# S04.net
KiCad netlist of a schematic drawn in Altium Designer
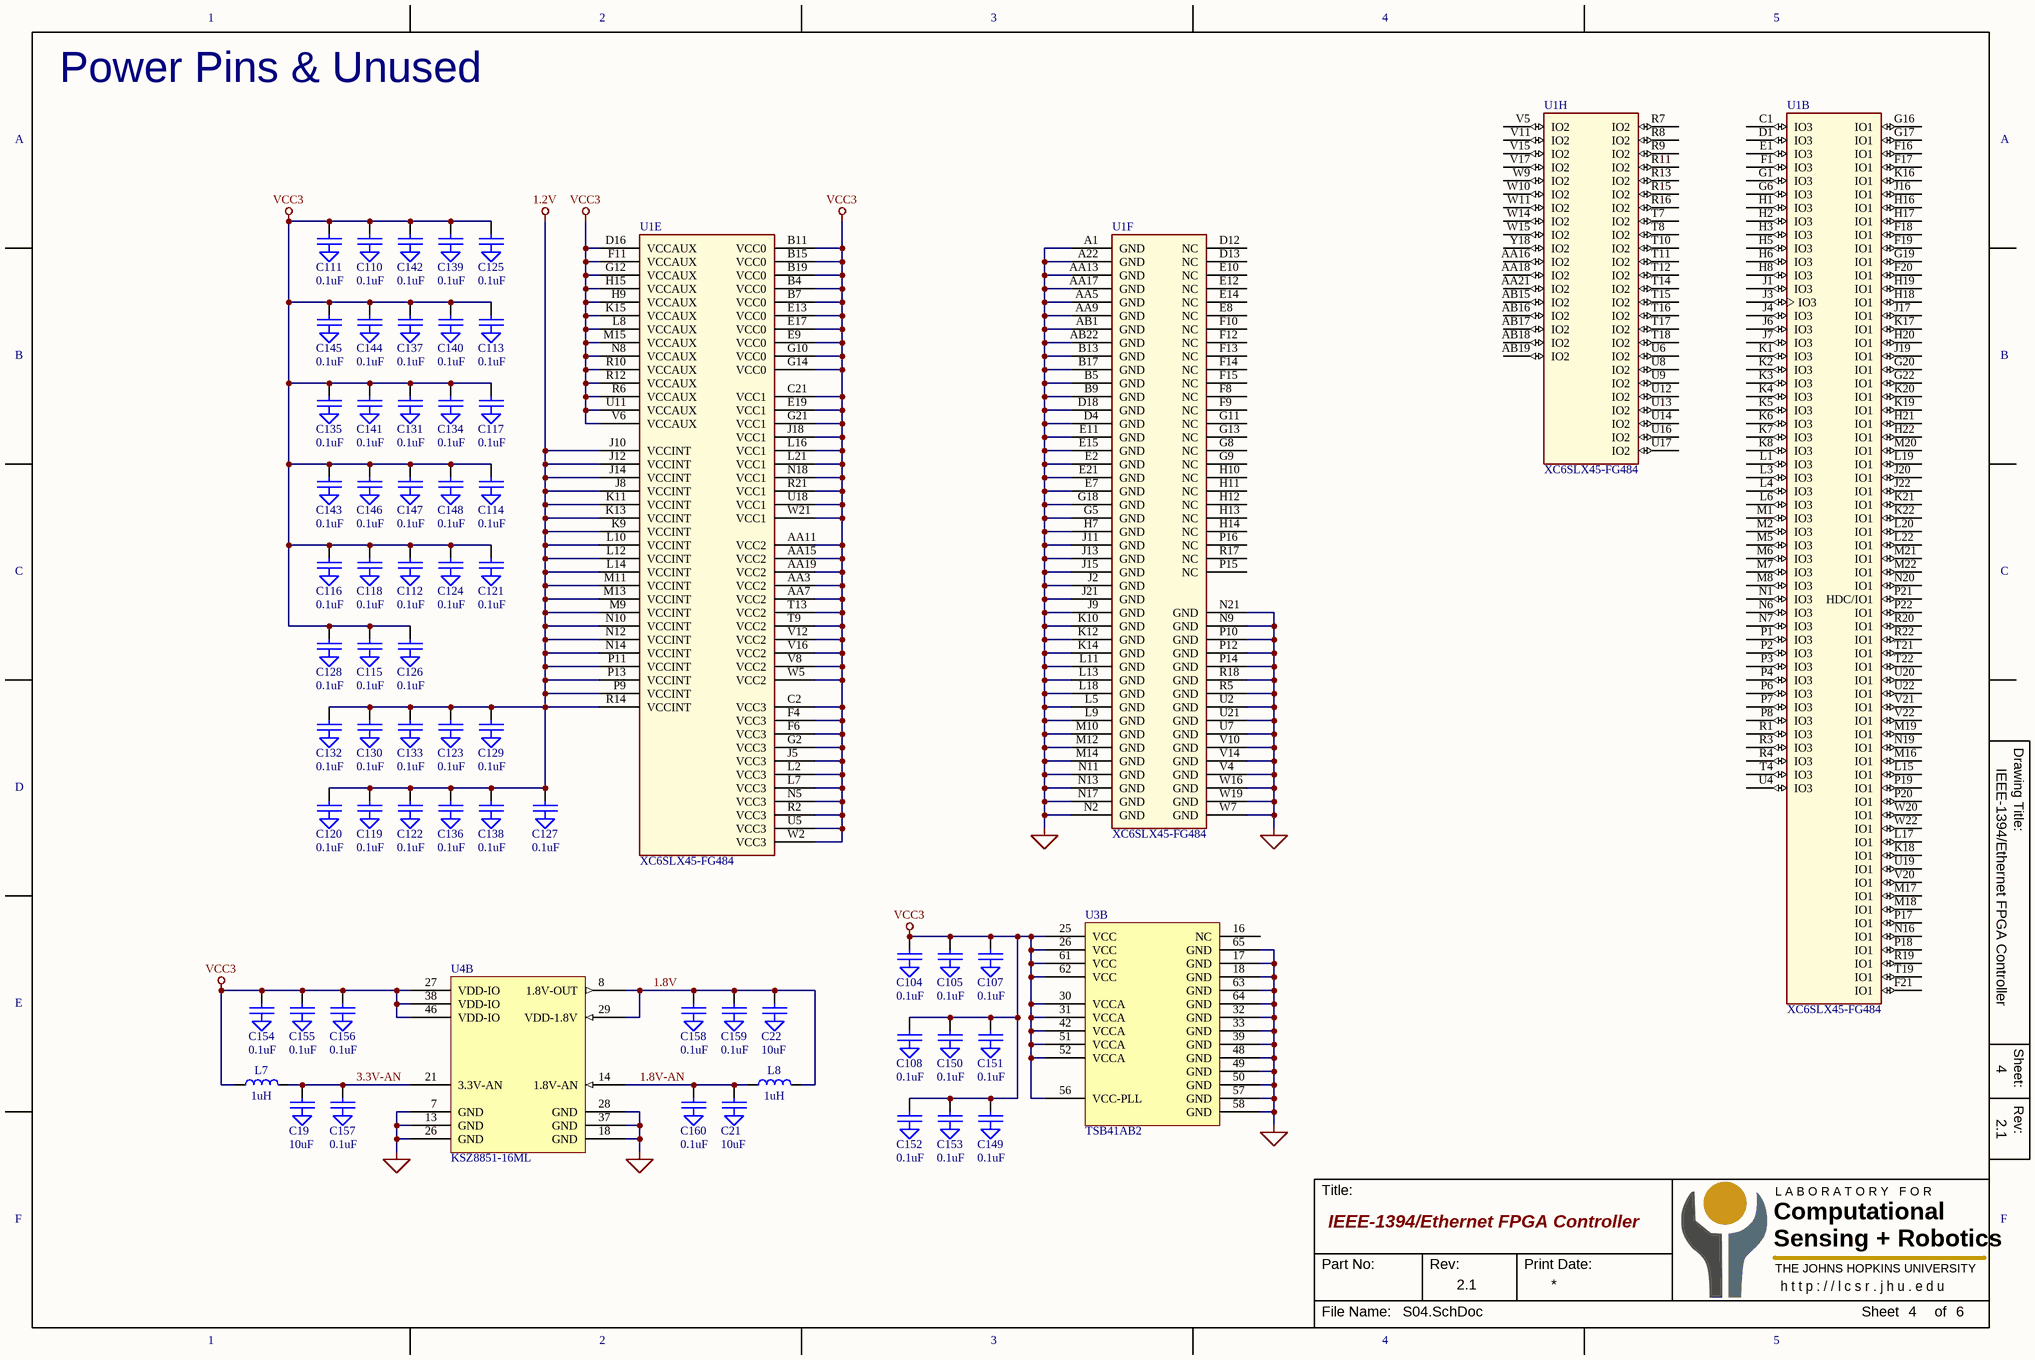
[diagram p0: S04.SchDoc]

(export (version "E")
  (design (tool "Eeschema 10.0.6"))
  (components
    (comp (ref "C19") (value "10uF") (footprint "C0603") (libsource (lib "LibJHU") (part "CAP-GND")))
    (comp (ref "C21") (value "10uF") (footprint "C0603") (libsource (lib "LibJHU") (part "CAP-GND")))
    (comp (ref "C22") (value "10uF") (footprint "C0603") (libsource (lib "LibJHU") (part "CAP-GND")))
    (comp (ref "C104") (value "0.1uF") (footprint "C0402") (libsource (lib "LibJHU") (part "CAP-GND")))
    (comp (ref "C105") (value "0.1uF") (footprint "C0402") (libsource (lib "LibJHU") (part "CAP-GND")))
    (comp (ref "C107") (value "0.1uF") (footprint "C0402") (libsource (lib "LibJHU") (part "CAP-GND")))
    (comp (ref "C108") (value "0.1uF") (footprint "C0402") (libsource (lib "LibJHU") (part "CAP-GND")))
    (comp (ref "C110") (value "0.1uF") (footprint "C0402") (libsource (lib "LibJHU") (part "CAP-GND")))
    (comp (ref "C111") (value "0.1uF") (footprint "C0402") (libsource (lib "LibJHU") (part "CAP-GND")))
    (comp (ref "C112") (value "0.1uF") (footprint "C0402") (libsource (lib "LibJHU") (part "CAP-GND")))
    (comp (ref "C113") (value "0.1uF") (footprint "C0402") (libsource (lib "LibJHU") (part "CAP-GND")))
    (comp (ref "C114") (value "0.1uF") (footprint "C0402") (libsource (lib "LibJHU") (part "CAP-GND")))
    (comp (ref "C115") (value "0.1uF") (footprint "C0402") (libsource (lib "LibJHU") (part "CAP-GND")))
    (comp (ref "C116") (value "0.1uF") (footprint "C0402") (libsource (lib "LibJHU") (part "CAP-GND")))
    (comp (ref "C117") (value "0.1uF") (footprint "C0402") (libsource (lib "LibJHU") (part "CAP-GND")))
    (comp (ref "C118") (value "0.1uF") (footprint "C0402") (libsource (lib "LibJHU") (part "CAP-GND")))
    (comp (ref "C119") (value "0.1uF") (footprint "C0402") (libsource (lib "LibJHU") (part "CAP-GND")))
    (comp (ref "C120") (value "0.1uF") (footprint "C0402") (libsource (lib "LibJHU") (part "CAP-GND")))
    (comp (ref "C121") (value "0.1uF") (footprint "C0402") (libsource (lib "LibJHU") (part "CAP-GND")))
    (comp (ref "C122") (value "0.1uF") (footprint "C0402") (libsource (lib "LibJHU") (part "CAP-GND")))
    (comp (ref "C123") (value "0.1uF") (footprint "C0402") (libsource (lib "LibJHU") (part "CAP-GND")))
    (comp (ref "C124") (value "0.1uF") (footprint "C0402") (libsource (lib "LibJHU") (part "CAP-GND")))
    (comp (ref "C125") (value "0.1uF") (footprint "C0402") (libsource (lib "LibJHU") (part "CAP-GND")))
    (comp (ref "C126") (value "0.1uF") (footprint "C0402") (libsource (lib "LibJHU") (part "CAP-GND")))
    (comp (ref "C127") (value "0.1uF") (footprint "C0402") (libsource (lib "LibJHU") (part "CAP-GND")))
    (comp (ref "C128") (value "0.1uF") (footprint "C0402") (libsource (lib "LibJHU") (part "CAP-GND")))
    (comp (ref "C129") (value "0.1uF") (footprint "C0402") (libsource (lib "LibJHU") (part "CAP-GND")))
    (comp (ref "C130") (value "0.1uF") (footprint "C0402") (libsource (lib "LibJHU") (part "CAP-GND")))
    (comp (ref "C131") (value "0.1uF") (footprint "C0402") (libsource (lib "LibJHU") (part "CAP-GND")))
    (comp (ref "C132") (value "0.1uF") (footprint "C0402") (libsource (lib "LibJHU") (part "CAP-GND")))
    (comp (ref "C133") (value "0.1uF") (footprint "C0402") (libsource (lib "LibJHU") (part "CAP-GND")))
    (comp (ref "C134") (value "0.1uF") (footprint "C0402") (libsource (lib "LibJHU") (part "CAP-GND")))
    (comp (ref "C135") (value "0.1uF") (footprint "C0402") (libsource (lib "LibJHU") (part "CAP-GND")))
    (comp (ref "C136") (value "0.1uF") (footprint "C0402") (libsource (lib "LibJHU") (part "CAP-GND")))
    (comp (ref "C137") (value "0.1uF") (footprint "C0402") (libsource (lib "LibJHU") (part "CAP-GND")))
    (comp (ref "C138") (value "0.1uF") (footprint "C0402") (libsource (lib "LibJHU") (part "CAP-GND")))
    (comp (ref "C139") (value "0.1uF") (footprint "C0402") (libsource (lib "LibJHU") (part "CAP-GND")))
    (comp (ref "C140") (value "0.1uF") (footprint "C0402") (libsource (lib "LibJHU") (part "CAP-GND")))
    (comp (ref "C141") (value "0.1uF") (footprint "C0402") (libsource (lib "LibJHU") (part "CAP-GND")))
    (comp (ref "C142") (value "0.1uF") (footprint "C0402") (libsource (lib "LibJHU") (part "CAP-GND")))
    (comp (ref "C143") (value "0.1uF") (footprint "C0402") (libsource (lib "LibJHU") (part "CAP-GND")))
    (comp (ref "C144") (value "0.1uF") (footprint "C0402") (libsource (lib "LibJHU") (part "CAP-GND")))
    (comp (ref "C145") (value "0.1uF") (footprint "C0402") (libsource (lib "LibJHU") (part "CAP-GND")))
    (comp (ref "C146") (value "0.1uF") (footprint "C0402") (libsource (lib "LibJHU") (part "CAP-GND")))
    (comp (ref "C147") (value "0.1uF") (footprint "C0402") (libsource (lib "LibJHU") (part "CAP-GND")))
    (comp (ref "C148") (value "0.1uF") (footprint "C0402") (libsource (lib "LibJHU") (part "CAP-GND")))
    (comp (ref "C149") (value "0.1uF") (footprint "C0402") (libsource (lib "LibJHU") (part "CAP-GND")))
    (comp (ref "C150") (value "0.1uF") (footprint "C0402") (libsource (lib "LibJHU") (part "CAP-GND")))
    (comp (ref "C151") (value "0.1uF") (footprint "C0402") (libsource (lib "LibJHU") (part "CAP-GND")))
    (comp (ref "C152") (value "0.1uF") (footprint "C0402") (libsource (lib "LibJHU") (part "CAP-GND")))
    (comp (ref "C153") (value "0.1uF") (footprint "C0402") (libsource (lib "LibJHU") (part "CAP-GND")))
    (comp (ref "C154") (value "0.1uF") (footprint "C0402") (libsource (lib "LibJHU") (part "CAP-GND")))
    (comp (ref "C155") (value "0.1uF") (footprint "C0402") (libsource (lib "LibJHU") (part "CAP-GND")))
    (comp (ref "C156") (value "0.1uF") (footprint "C0402") (libsource (lib "LibJHU") (part "CAP-GND")))
    (comp (ref "C157") (value "0.1uF") (footprint "C0402") (libsource (lib "LibJHU") (part "CAP-GND")))
    (comp (ref "C158") (value "0.1uF") (footprint "C0402") (libsource (lib "LibJHU") (part "CAP-GND")))
    (comp (ref "C159") (value "0.1uF") (footprint "C0402") (libsource (lib "LibJHU") (part "CAP-GND")))
    (comp (ref "C160") (value "0.1uF") (footprint "C0402") (libsource (lib "LibJHU") (part "CAP-GND")))
    (comp (ref "L7") (value "1uH") (footprint "L0603") (libsource (lib "LibJHU") (part "INDUCTOR")))
    (comp (ref "L8") (value "1uH") (footprint "L0603") (libsource (lib "LibJHU") (part "INDUCTOR")))
    (comp (ref "U1")
      (value "XC6SLX45-FG484")
      (footprint "FG-484")
      (libsource (lib "LibJHU") (part "XC6SLX45-FG484"))
    )
    (comp (ref "U3")
      (value "TSB41AB2")
      (footprint "PQFP-65")
      (description "IEEE 1394a-2000 Two-port Transceiver/Arbiter")
      (libsource (lib "LibJHU") (part "TSB41AB2"))
    )
    (comp (ref "U4")
      (value "KSZ8851-16ML")
      (footprint "QFP-48-7MM")
      (libsource (lib "LibJHU") (part "KSZ8851-16ML"))
    )
  )
  (nets
    (net (code "1") (name "/1.8V") (class "Default")
      (node (ref "C158") (pin "1") (pintype "passive"))
      (node (ref "C159") (pin "1") (pintype "passive"))
      (node (ref "C22") (pin "1") (pintype "passive"))
      (node (ref "L8") (pin "2") (pintype "passive"))
      (node (ref "U4") (pin "29") (pinfunction "VDD-1.8V_29") (pintype "input"))
      (node (ref "U4") (pin "8") (pinfunction "1.8V-OUT_8") (pintype "output"))
    )
    (net (code "2") (name "/1.8V-AN") (class "Default")
      (node (ref "C160") (pin "1") (pintype "passive"))
      (node (ref "C21") (pin "1") (pintype "passive"))
      (node (ref "L8") (pin "1") (pintype "passive"))
      (node (ref "U4") (pin "14") (pinfunction "1.8V-AN_14") (pintype "input"))
    )
    (net (code "3") (name "/3.3V-AN") (class "Default")
      (node (ref "C157") (pin "1") (pintype "passive"))
      (node (ref "C19") (pin "1") (pintype "passive"))
      (node (ref "L7") (pin "2") (pintype "passive"))
      (node (ref "U4") (pin "21") (pinfunction "3.3V-AN_21") (pintype "power_in"))
    )
    (net (code "4") (name "1.2V") (class "Default")
      (node (ref "C119") (pin "1") (pintype "passive"))
      (node (ref "C120") (pin "1") (pintype "passive"))
      (node (ref "C122") (pin "1") (pintype "passive"))
      (node (ref "C123") (pin "1") (pintype "passive"))
      (node (ref "C127") (pin "1") (pintype "passive"))
      (node (ref "C129") (pin "1") (pintype "passive"))
      (node (ref "C130") (pin "1") (pintype "passive"))
      (node (ref "C132") (pin "1") (pintype "passive"))
      (node (ref "C133") (pin "1") (pintype "passive"))
      (node (ref "C136") (pin "1") (pintype "passive"))
      (node (ref "C138") (pin "1") (pintype "passive"))
      (node (ref "U1") (pin "J10") (pinfunction "VCCINT_J10") (pintype "power_in"))
      (node (ref "U1") (pin "J12") (pinfunction "VCCINT_J12") (pintype "power_in"))
      (node (ref "U1") (pin "J14") (pinfunction "VCCINT_J14") (pintype "power_in"))
      (node (ref "U1") (pin "J8") (pinfunction "VCCINT_J8") (pintype "power_in"))
      (node (ref "U1") (pin "K11") (pinfunction "VCCINT_K11") (pintype "power_in"))
      (node (ref "U1") (pin "K13") (pinfunction "VCCINT_K13") (pintype "power_in"))
      (node (ref "U1") (pin "K9") (pinfunction "VCCINT_K9") (pintype "power_in"))
      (node (ref "U1") (pin "L10") (pinfunction "VCCINT_L10") (pintype "power_in"))
      (node (ref "U1") (pin "L12") (pinfunction "VCCINT_L12") (pintype "power_in"))
      (node (ref "U1") (pin "L14") (pinfunction "VCCINT_L14") (pintype "power_in"))
      (node (ref "U1") (pin "M11") (pinfunction "VCCINT_M11") (pintype "power_in"))
      (node (ref "U1") (pin "M13") (pinfunction "VCCINT_M13") (pintype "power_in"))
      (node (ref "U1") (pin "M9") (pinfunction "VCCINT_M9") (pintype "power_in"))
      (node (ref "U1") (pin "N10") (pinfunction "VCCINT_N10") (pintype "power_in"))
      (node (ref "U1") (pin "N12") (pinfunction "VCCINT_N12") (pintype "power_in"))
      (node (ref "U1") (pin "N14") (pinfunction "VCCINT_N14") (pintype "power_in"))
      (node (ref "U1") (pin "P11") (pinfunction "VCCINT_P11") (pintype "power_in"))
      (node (ref "U1") (pin "P13") (pinfunction "VCCINT_P13") (pintype "power_in"))
      (node (ref "U1") (pin "P9") (pinfunction "VCCINT_P9") (pintype "power_in"))
      (node (ref "U1") (pin "R14") (pinfunction "VCCINT_R14") (pintype "power_in"))
    )
    (net (code "5") (name "GND") (class "Default")
      (node (ref "C104") (pin "2") (pinfunction "GND_2") (pintype "power_in"))
      (node (ref "C105") (pin "2") (pinfunction "GND_2") (pintype "power_in"))
      (node (ref "C107") (pin "2") (pinfunction "GND_2") (pintype "power_in"))
      (node (ref "C108") (pin "2") (pinfunction "GND_2") (pintype "power_in"))
      (node (ref "C110") (pin "2") (pinfunction "GND_2") (pintype "power_in"))
      (node (ref "C111") (pin "2") (pinfunction "GND_2") (pintype "power_in"))
      (node (ref "C112") (pin "2") (pinfunction "GND_2") (pintype "power_in"))
      (node (ref "C113") (pin "2") (pinfunction "GND_2") (pintype "power_in"))
      (node (ref "C114") (pin "2") (pinfunction "GND_2") (pintype "power_in"))
      (node (ref "C115") (pin "2") (pinfunction "GND_2") (pintype "power_in"))
      (node (ref "C116") (pin "2") (pinfunction "GND_2") (pintype "power_in"))
      (node (ref "C117") (pin "2") (pinfunction "GND_2") (pintype "power_in"))
      (node (ref "C118") (pin "2") (pinfunction "GND_2") (pintype "power_in"))
      (node (ref "C119") (pin "2") (pinfunction "GND_2") (pintype "power_in"))
      (node (ref "C120") (pin "2") (pinfunction "GND_2") (pintype "power_in"))
      (node (ref "C121") (pin "2") (pinfunction "GND_2") (pintype "power_in"))
      (node (ref "C122") (pin "2") (pinfunction "GND_2") (pintype "power_in"))
      (node (ref "C123") (pin "2") (pinfunction "GND_2") (pintype "power_in"))
      (node (ref "C124") (pin "2") (pinfunction "GND_2") (pintype "power_in"))
      (node (ref "C125") (pin "2") (pinfunction "GND_2") (pintype "power_in"))
      (node (ref "C126") (pin "2") (pinfunction "GND_2") (pintype "power_in"))
      (node (ref "C127") (pin "2") (pinfunction "GND_2") (pintype "power_in"))
      (node (ref "C128") (pin "2") (pinfunction "GND_2") (pintype "power_in"))
      (node (ref "C129") (pin "2") (pinfunction "GND_2") (pintype "power_in"))
      (node (ref "C130") (pin "2") (pinfunction "GND_2") (pintype "power_in"))
      (node (ref "C131") (pin "2") (pinfunction "GND_2") (pintype "power_in"))
      (node (ref "C132") (pin "2") (pinfunction "GND_2") (pintype "power_in"))
      (node (ref "C133") (pin "2") (pinfunction "GND_2") (pintype "power_in"))
      (node (ref "C134") (pin "2") (pinfunction "GND_2") (pintype "power_in"))
      (node (ref "C135") (pin "2") (pinfunction "GND_2") (pintype "power_in"))
      (node (ref "C136") (pin "2") (pinfunction "GND_2") (pintype "power_in"))
      (node (ref "C137") (pin "2") (pinfunction "GND_2") (pintype "power_in"))
      (node (ref "C138") (pin "2") (pinfunction "GND_2") (pintype "power_in"))
      (node (ref "C139") (pin "2") (pinfunction "GND_2") (pintype "power_in"))
      (node (ref "C140") (pin "2") (pinfunction "GND_2") (pintype "power_in"))
      (node (ref "C141") (pin "2") (pinfunction "GND_2") (pintype "power_in"))
      (node (ref "C142") (pin "2") (pinfunction "GND_2") (pintype "power_in"))
      (node (ref "C143") (pin "2") (pinfunction "GND_2") (pintype "power_in"))
      (node (ref "C144") (pin "2") (pinfunction "GND_2") (pintype "power_in"))
      (node (ref "C145") (pin "2") (pinfunction "GND_2") (pintype "power_in"))
      (node (ref "C146") (pin "2") (pinfunction "GND_2") (pintype "power_in"))
      (node (ref "C147") (pin "2") (pinfunction "GND_2") (pintype "power_in"))
      (node (ref "C148") (pin "2") (pinfunction "GND_2") (pintype "power_in"))
      (node (ref "C149") (pin "2") (pinfunction "GND_2") (pintype "power_in"))
      (node (ref "C150") (pin "2") (pinfunction "GND_2") (pintype "power_in"))
      (node (ref "C151") (pin "2") (pinfunction "GND_2") (pintype "power_in"))
      (node (ref "C152") (pin "2") (pinfunction "GND_2") (pintype "power_in"))
      (node (ref "C153") (pin "2") (pinfunction "GND_2") (pintype "power_in"))
      (node (ref "C154") (pin "2") (pinfunction "GND_2") (pintype "power_in"))
      (node (ref "C155") (pin "2") (pinfunction "GND_2") (pintype "power_in"))
      (node (ref "C156") (pin "2") (pinfunction "GND_2") (pintype "power_in"))
      (node (ref "C157") (pin "2") (pinfunction "GND_2") (pintype "power_in"))
      (node (ref "C158") (pin "2") (pinfunction "GND_2") (pintype "power_in"))
      (node (ref "C159") (pin "2") (pinfunction "GND_2") (pintype "power_in"))
      (node (ref "C160") (pin "2") (pinfunction "GND_2") (pintype "power_in"))
      (node (ref "C19") (pin "2") (pinfunction "GND_2") (pintype "power_in"))
      (node (ref "C21") (pin "2") (pinfunction "GND_2") (pintype "power_in"))
      (node (ref "C22") (pin "2") (pinfunction "GND_2") (pintype "power_in"))
      (node (ref "U1") (pin "A1") (pinfunction "GND_A1") (pintype "power_in"))
      (node (ref "U1") (pin "A22") (pinfunction "GND_A22") (pintype "power_in"))
      (node (ref "U1") (pin "AA13") (pinfunction "GND_AA13") (pintype "power_in"))
      (node (ref "U1") (pin "AA17") (pinfunction "GND_AA17") (pintype "power_in"))
      (node (ref "U1") (pin "AA5") (pinfunction "GND_AA5") (pintype "power_in"))
      (node (ref "U1") (pin "AA9") (pinfunction "GND_AA9") (pintype "power_in"))
      (node (ref "U1") (pin "AB1") (pinfunction "GND_AB1") (pintype "power_in"))
      (node (ref "U1") (pin "AB22") (pinfunction "GND_AB22") (pintype "power_in"))
      (node (ref "U1") (pin "B13") (pinfunction "GND_B13") (pintype "power_in"))
      (node (ref "U1") (pin "B17") (pinfunction "GND_B17") (pintype "power_in"))
      (node (ref "U1") (pin "B5") (pinfunction "GND_B5") (pintype "power_in"))
      (node (ref "U1") (pin "B9") (pinfunction "GND_B9") (pintype "power_in"))
      (node (ref "U1") (pin "D18") (pinfunction "GND_D18") (pintype "power_in"))
      (node (ref "U1") (pin "D4") (pinfunction "GND_D4") (pintype "power_in"))
      (node (ref "U1") (pin "E11") (pinfunction "GND_E11") (pintype "power_in"))
      (node (ref "U1") (pin "E15") (pinfunction "GND_E15") (pintype "power_in"))
      (node (ref "U1") (pin "E2") (pinfunction "GND_E2") (pintype "power_in"))
      (node (ref "U1") (pin "E21") (pinfunction "GND_E21") (pintype "power_in"))
      (node (ref "U1") (pin "E7") (pinfunction "GND_E7") (pintype "power_in"))
      (node (ref "U1") (pin "G18") (pinfunction "GND_G18") (pintype "power_in"))
      (node (ref "U1") (pin "G5") (pinfunction "GND_G5") (pintype "power_in"))
      (node (ref "U1") (pin "H7") (pinfunction "GND_H7") (pintype "power_in"))
      (node (ref "U1") (pin "J11") (pinfunction "GND_J11") (pintype "power_in"))
      (node (ref "U1") (pin "J13") (pinfunction "GND_J13") (pintype "power_in"))
      (node (ref "U1") (pin "J15") (pinfunction "GND_J15") (pintype "power_in"))
      (node (ref "U1") (pin "J2") (pinfunction "GND_J2") (pintype "power_in"))
      (node (ref "U1") (pin "J21") (pinfunction "GND_J21") (pintype "power_in"))
      (node (ref "U1") (pin "J9") (pinfunction "GND_J9") (pintype "power_in"))
      (node (ref "U1") (pin "K10") (pinfunction "GND_K10") (pintype "power_in"))
      (node (ref "U1") (pin "K12") (pinfunction "GND_K12") (pintype "power_in"))
      (node (ref "U1") (pin "K14") (pinfunction "GND_K14") (pintype "power_in"))
      (node (ref "U1") (pin "L11") (pinfunction "GND_L11") (pintype "power_in"))
      (node (ref "U1") (pin "L13") (pinfunction "GND_L13") (pintype "power_in"))
      (node (ref "U1") (pin "L18") (pinfunction "GND_L18") (pintype "power_in"))
      (node (ref "U1") (pin "L5") (pinfunction "GND_L5") (pintype "power_in"))
      (node (ref "U1") (pin "L9") (pinfunction "GND_L9") (pintype "power_in"))
      (node (ref "U1") (pin "M10") (pinfunction "GND_M10") (pintype "power_in"))
      (node (ref "U1") (pin "M12") (pinfunction "GND_M12") (pintype "power_in"))
      (node (ref "U1") (pin "M14") (pinfunction "GND_M14") (pintype "power_in"))
      (node (ref "U1") (pin "N11") (pinfunction "GND_N11") (pintype "power_in"))
      (node (ref "U1") (pin "N13") (pinfunction "GND_N13") (pintype "power_in"))
      (node (ref "U1") (pin "N17") (pinfunction "GND_N17") (pintype "power_in"))
      (node (ref "U1") (pin "N2") (pinfunction "GND_N2") (pintype "power_in"))
      (node (ref "U1") (pin "N21") (pinfunction "GND_N21") (pintype "power_in"))
      (node (ref "U1") (pin "N9") (pinfunction "GND_N9") (pintype "power_in"))
      (node (ref "U1") (pin "P10") (pinfunction "GND_P10") (pintype "power_in"))
      (node (ref "U1") (pin "P12") (pinfunction "GND_P12") (pintype "power_in"))
      (node (ref "U1") (pin "P14") (pinfunction "GND_P14") (pintype "power_in"))
      (node (ref "U1") (pin "R18") (pinfunction "GND_R18") (pintype "power_in"))
      (node (ref "U1") (pin "R5") (pinfunction "GND_R5") (pintype "power_in"))
      (node (ref "U1") (pin "U2") (pinfunction "GND_U2") (pintype "power_in"))
      (node (ref "U1") (pin "U21") (pinfunction "GND_U21") (pintype "power_in"))
      (node (ref "U1") (pin "U7") (pinfunction "GND_U7") (pintype "power_in"))
      (node (ref "U1") (pin "V10") (pinfunction "GND_V10") (pintype "power_in"))
      (node (ref "U1") (pin "V14") (pinfunction "GND_V14") (pintype "power_in"))
      (node (ref "U1") (pin "V4") (pinfunction "GND_V4") (pintype "power_in"))
      (node (ref "U1") (pin "W16") (pinfunction "GND_W16") (pintype "power_in"))
      (node (ref "U1") (pin "W19") (pinfunction "GND_W19") (pintype "power_in"))
      (node (ref "U1") (pin "W7") (pinfunction "GND_W7") (pintype "power_in"))
      (node (ref "U3") (pin "17") (pinfunction "GND_17") (pintype "power_in"))
      (node (ref "U3") (pin "18") (pinfunction "GND_18") (pintype "power_in"))
      (node (ref "U3") (pin "32") (pinfunction "GND_32") (pintype "power_in"))
      (node (ref "U3") (pin "33") (pinfunction "GND_33") (pintype "power_in"))
      (node (ref "U3") (pin "39") (pinfunction "GND_39") (pintype "power_in"))
      (node (ref "U3") (pin "48") (pinfunction "GND_48") (pintype "power_in"))
      (node (ref "U3") (pin "49") (pinfunction "GND_49") (pintype "power_in"))
      (node (ref "U3") (pin "50") (pinfunction "GND_50") (pintype "power_in"))
      (node (ref "U3") (pin "57") (pinfunction "GND_57") (pintype "power_in"))
      (node (ref "U3") (pin "58") (pinfunction "GND_58") (pintype "power_in"))
      (node (ref "U3") (pin "63") (pinfunction "GND_63") (pintype "power_in"))
      (node (ref "U3") (pin "64") (pinfunction "GND_64") (pintype "power_in"))
      (node (ref "U3") (pin "65") (pinfunction "GND_65") (pintype "power_in"))
      (node (ref "U4") (pin "13") (pinfunction "GND_13") (pintype "power_in"))
      (node (ref "U4") (pin "18") (pinfunction "GND_18") (pintype "power_in"))
      (node (ref "U4") (pin "26") (pinfunction "GND_26") (pintype "power_in"))
      (node (ref "U4") (pin "28") (pinfunction "GND_28") (pintype "power_in"))
      (node (ref "U4") (pin "37") (pinfunction "GND_37") (pintype "power_in"))
      (node (ref "U4") (pin "7") (pinfunction "GND_7") (pintype "power_in"))
    )
    (net (code "6") (name "VCC3") (class "Default")
      (node (ref "C104") (pin "1") (pintype "passive"))
      (node (ref "C105") (pin "1") (pintype "passive"))
      (node (ref "C107") (pin "1") (pintype "passive"))
      (node (ref "C108") (pin "1") (pintype "passive"))
      (node (ref "C110") (pin "1") (pintype "passive"))
      (node (ref "C111") (pin "1") (pintype "passive"))
      (node (ref "C112") (pin "1") (pintype "passive"))
      (node (ref "C113") (pin "1") (pintype "passive"))
      (node (ref "C114") (pin "1") (pintype "passive"))
      (node (ref "C115") (pin "1") (pintype "passive"))
      (node (ref "C116") (pin "1") (pintype "passive"))
      (node (ref "C117") (pin "1") (pintype "passive"))
      (node (ref "C118") (pin "1") (pintype "passive"))
      (node (ref "C121") (pin "1") (pintype "passive"))
      (node (ref "C124") (pin "1") (pintype "passive"))
      (node (ref "C125") (pin "1") (pintype "passive"))
      (node (ref "C126") (pin "1") (pintype "passive"))
      (node (ref "C128") (pin "1") (pintype "passive"))
      (node (ref "C131") (pin "1") (pintype "passive"))
      (node (ref "C134") (pin "1") (pintype "passive"))
      (node (ref "C135") (pin "1") (pintype "passive"))
      (node (ref "C137") (pin "1") (pintype "passive"))
      (node (ref "C139") (pin "1") (pintype "passive"))
      (node (ref "C140") (pin "1") (pintype "passive"))
      (node (ref "C141") (pin "1") (pintype "passive"))
      (node (ref "C142") (pin "1") (pintype "passive"))
      (node (ref "C143") (pin "1") (pintype "passive"))
      (node (ref "C144") (pin "1") (pintype "passive"))
      (node (ref "C145") (pin "1") (pintype "passive"))
      (node (ref "C146") (pin "1") (pintype "passive"))
      (node (ref "C147") (pin "1") (pintype "passive"))
      (node (ref "C148") (pin "1") (pintype "passive"))
      (node (ref "C149") (pin "1") (pintype "passive"))
      (node (ref "C150") (pin "1") (pintype "passive"))
      (node (ref "C151") (pin "1") (pintype "passive"))
      (node (ref "C152") (pin "1") (pintype "passive"))
      (node (ref "C153") (pin "1") (pintype "passive"))
      (node (ref "C154") (pin "1") (pintype "passive"))
      (node (ref "C155") (pin "1") (pintype "passive"))
      (node (ref "C156") (pin "1") (pintype "passive"))
      (node (ref "L7") (pin "1") (pintype "passive"))
      (node (ref "U1") (pin "AA11") (pinfunction "VCC2_AA11") (pintype "power_in"))
      (node (ref "U1") (pin "AA15") (pinfunction "VCC2_AA15") (pintype "power_in"))
      (node (ref "U1") (pin "AA19") (pinfunction "VCC2_AA19") (pintype "power_in"))
      (node (ref "U1") (pin "AA3") (pinfunction "VCC2_AA3") (pintype "power_in"))
      (node (ref "U1") (pin "AA7") (pinfunction "VCC2_AA7") (pintype "power_in"))
      (node (ref "U1") (pin "B11") (pinfunction "VCC0_B11") (pintype "power_in"))
      (node (ref "U1") (pin "B15") (pinfunction "VCC0_B15") (pintype "power_in"))
      (node (ref "U1") (pin "B19") (pinfunction "VCC0_B19") (pintype "power_in"))
      (node (ref "U1") (pin "B4") (pinfunction "VCC0_B4") (pintype "power_in"))
      (node (ref "U1") (pin "B7") (pinfunction "VCC0_B7") (pintype "power_in"))
      (node (ref "U1") (pin "C2") (pinfunction "VCC3_C2") (pintype "power_in"))
      (node (ref "U1") (pin "C21") (pinfunction "VCC1_C21") (pintype "power_in"))
      (node (ref "U1") (pin "D16") (pinfunction "VCCAUX_D16") (pintype "power_in"))
      (node (ref "U1") (pin "E13") (pinfunction "VCC0_E13") (pintype "power_in"))
      (node (ref "U1") (pin "E17") (pinfunction "VCC0_E17") (pintype "power_in"))
      (node (ref "U1") (pin "E19") (pinfunction "VCC1_E19") (pintype "power_in"))
      (node (ref "U1") (pin "E9") (pinfunction "VCC0_E9") (pintype "power_in"))
      (node (ref "U1") (pin "F11") (pinfunction "VCCAUX_F11") (pintype "power_in"))
      (node (ref "U1") (pin "F4") (pinfunction "VCC3_F4") (pintype "power_in"))
      (node (ref "U1") (pin "F6") (pinfunction "VCC3_F6") (pintype "power_in"))
      (node (ref "U1") (pin "G10") (pinfunction "VCC0_G10") (pintype "power_in"))
      (node (ref "U1") (pin "G12") (pinfunction "VCCAUX_G12") (pintype "power_in"))
      (node (ref "U1") (pin "G14") (pinfunction "VCC0_G14") (pintype "power_in"))
      (node (ref "U1") (pin "G2") (pinfunction "VCC3_G2") (pintype "power_in"))
      (node (ref "U1") (pin "G21") (pinfunction "VCC1_G21") (pintype "power_in"))
      (node (ref "U1") (pin "H15") (pinfunction "VCCAUX_H15") (pintype "power_in"))
      (node (ref "U1") (pin "H9") (pinfunction "VCCAUX_H9") (pintype "power_in"))
      (node (ref "U1") (pin "J18") (pinfunction "VCC1_J18") (pintype "power_in"))
      (node (ref "U1") (pin "J5") (pinfunction "VCC3_J5") (pintype "power_in"))
      (node (ref "U1") (pin "K15") (pinfunction "VCCAUX_K15") (pintype "power_in"))
      (node (ref "U1") (pin "L16") (pinfunction "VCC1_L16") (pintype "power_in"))
      (node (ref "U1") (pin "L2") (pinfunction "VCC3_L2") (pintype "power_in"))
      (node (ref "U1") (pin "L21") (pinfunction "VCC1_L21") (pintype "power_in"))
      (node (ref "U1") (pin "L7") (pinfunction "VCC3_L7") (pintype "power_in"))
      (node (ref "U1") (pin "L8") (pinfunction "VCCAUX_L8") (pintype "power_in"))
      (node (ref "U1") (pin "M15") (pinfunction "VCCAUX_M15") (pintype "power_in"))
      (node (ref "U1") (pin "N18") (pinfunction "VCC1_N18") (pintype "power_in"))
      (node (ref "U1") (pin "N5") (pinfunction "VCC3_N5") (pintype "power_in"))
      (node (ref "U1") (pin "N8") (pinfunction "VCCAUX_N8") (pintype "power_in"))
      (node (ref "U1") (pin "R10") (pinfunction "VCCAUX_R10") (pintype "power_in"))
      (node (ref "U1") (pin "R12") (pinfunction "VCCAUX_R12") (pintype "power_in"))
      (node (ref "U1") (pin "R2") (pinfunction "VCC3_R2") (pintype "power_in"))
      (node (ref "U1") (pin "R21") (pinfunction "VCC1_R21") (pintype "power_in"))
      (node (ref "U1") (pin "R6") (pinfunction "VCCAUX_R6") (pintype "power_in"))
      (node (ref "U1") (pin "T13") (pinfunction "VCC2_T13") (pintype "power_in"))
      (node (ref "U1") (pin "T9") (pinfunction "VCC2_T9") (pintype "power_in"))
      (node (ref "U1") (pin "U11") (pinfunction "VCCAUX_U11") (pintype "power_in"))
      (node (ref "U1") (pin "U18") (pinfunction "VCC1_U18") (pintype "power_in"))
      (node (ref "U1") (pin "U5") (pinfunction "VCC3_U5") (pintype "power_in"))
      (node (ref "U1") (pin "V12") (pinfunction "VCC2_V12") (pintype "power_in"))
      (node (ref "U1") (pin "V16") (pinfunction "VCC2_V16") (pintype "power_in"))
      (node (ref "U1") (pin "V6") (pinfunction "VCCAUX_V6") (pintype "power_in"))
      (node (ref "U1") (pin "V8") (pinfunction "VCC2_V8") (pintype "power_in"))
      (node (ref "U1") (pin "W2") (pinfunction "VCC3_W2") (pintype "power_in"))
      (node (ref "U1") (pin "W21") (pinfunction "VCC1_W21") (pintype "power_in"))
      (node (ref "U1") (pin "W5") (pinfunction "VCC2_W5") (pintype "power_in"))
      (node (ref "U3") (pin "25") (pinfunction "VCC_25") (pintype "power_in"))
      (node (ref "U3") (pin "26") (pinfunction "VCC_26") (pintype "power_in"))
      (node (ref "U3") (pin "30") (pinfunction "VCCA_30") (pintype "power_in"))
      (node (ref "U3") (pin "31") (pinfunction "VCCA_31") (pintype "power_in"))
      (node (ref "U3") (pin "42") (pinfunction "VCCA_42") (pintype "power_in"))
      (node (ref "U3") (pin "51") (pinfunction "VCCA_51") (pintype "power_in"))
      (node (ref "U3") (pin "52") (pinfunction "VCCA_52") (pintype "power_in"))
      (node (ref "U3") (pin "56") (pinfunction "VCC-PLL_56") (pintype "power_in"))
      (node (ref "U3") (pin "61") (pinfunction "VCC_61") (pintype "power_in"))
      (node (ref "U3") (pin "62") (pinfunction "VCC_62") (pintype "power_in"))
      (node (ref "U4") (pin "27") (pinfunction "VDD-IO_27") (pintype "power_in"))
      (node (ref "U4") (pin "38") (pinfunction "VDD-IO_38") (pintype "power_in"))
      (node (ref "U4") (pin "46") (pinfunction "VDD-IO_46") (pintype "power_in"))
    )
    (net (code "7") (name "unconnected-(U1B-HDC{slash}IO1-PadP21)") (class "Default")
      (node (ref "U1") (pin "P21") (pinfunction "HDC/IO1_P21") (pintype "bidirectional"))
    )
    (net (code "8") (name "unconnected-(U1B-IO1-PadF16)") (class "Default")
      (node (ref "U1") (pin "F16") (pinfunction "IO1_F16") (pintype "bidirectional"))
    )
    (net (code "9") (name "unconnected-(U1B-IO1-PadF17)") (class "Default")
      (node (ref "U1") (pin "F17") (pinfunction "IO1_F17") (pintype "bidirectional"))
    )
    (net (code "10") (name "unconnected-(U1B-IO1-PadF18)") (class "Default")
      (node (ref "U1") (pin "F18") (pinfunction "IO1_F18") (pintype "bidirectional"))
    )
    (net (code "11") (name "unconnected-(U1B-IO1-PadF19)") (class "Default")
      (node (ref "U1") (pin "F19") (pinfunction "IO1_F19") (pintype "bidirectional"))
    )
    (net (code "12") (name "unconnected-(U1B-IO1-PadF20)") (class "Default")
      (node (ref "U1") (pin "F20") (pinfunction "IO1_F20") (pintype "bidirectional"))
    )
    (net (code "13") (name "unconnected-(U1B-IO1-PadF21)") (class "Default")
      (node (ref "U1") (pin "F21") (pinfunction "IO1_F21") (pintype "bidirectional"))
    )
    (net (code "14") (name "unconnected-(U1B-IO1-PadG16)") (class "Default")
      (node (ref "U1") (pin "G16") (pinfunction "IO1_G16") (pintype "bidirectional"))
    )
    (net (code "15") (name "unconnected-(U1B-IO1-PadG17)") (class "Default")
      (node (ref "U1") (pin "G17") (pinfunction "IO1_G17") (pintype "bidirectional"))
    )
    (net (code "16") (name "unconnected-(U1B-IO1-PadG19)") (class "Default")
      (node (ref "U1") (pin "G19") (pinfunction "IO1_G19") (pintype "bidirectional"))
    )
    (net (code "17") (name "unconnected-(U1B-IO1-PadG20)") (class "Default")
      (node (ref "U1") (pin "G20") (pinfunction "IO1_G20") (pintype "bidirectional"))
    )
    (net (code "18") (name "unconnected-(U1B-IO1-PadG22)") (class "Default")
      (node (ref "U1") (pin "G22") (pinfunction "IO1_G22") (pintype "bidirectional"))
    )
    (net (code "19") (name "unconnected-(U1B-IO1-PadH16)") (class "Default")
      (node (ref "U1") (pin "H16") (pinfunction "IO1_H16") (pintype "bidirectional"))
    )
    (net (code "20") (name "unconnected-(U1B-IO1-PadH17)") (class "Default")
      (node (ref "U1") (pin "H17") (pinfunction "IO1_H17") (pintype "bidirectional"))
    )
    (net (code "21") (name "unconnected-(U1B-IO1-PadH18)") (class "Default")
      (node (ref "U1") (pin "H18") (pinfunction "IO1_H18") (pintype "bidirectional"))
    )
    (net (code "22") (name "unconnected-(U1B-IO1-PadH19)") (class "Default")
      (node (ref "U1") (pin "H19") (pinfunction "IO1_H19") (pintype "bidirectional"))
    )
    (net (code "23") (name "unconnected-(U1B-IO1-PadH20)") (class "Default")
      (node (ref "U1") (pin "H20") (pinfunction "IO1_H20") (pintype "bidirectional"))
    )
    (net (code "24") (name "unconnected-(U1B-IO1-PadH21)") (class "Default")
      (node (ref "U1") (pin "H21") (pinfunction "IO1_H21") (pintype "bidirectional"))
    )
    (net (code "25") (name "unconnected-(U1B-IO1-PadH22)") (class "Default")
      (node (ref "U1") (pin "H22") (pinfunction "IO1_H22") (pintype "bidirectional"))
    )
    (net (code "26") (name "unconnected-(U1B-IO1-PadJ16)") (class "Default")
      (node (ref "U1") (pin "J16") (pinfunction "IO1_J16") (pintype "bidirectional"))
    )
    (net (code "27") (name "unconnected-(U1B-IO1-PadJ17)") (class "Default")
      (node (ref "U1") (pin "J17") (pinfunction "IO1_J17") (pintype "bidirectional"))
    )
    (net (code "28") (name "unconnected-(U1B-IO1-PadJ19)") (class "Default")
      (node (ref "U1") (pin "J19") (pinfunction "IO1_J19") (pintype "bidirectional"))
    )
    (net (code "29") (name "unconnected-(U1B-IO1-PadJ20)") (class "Default")
      (node (ref "U1") (pin "J20") (pinfunction "IO1_J20") (pintype "bidirectional"))
    )
    (net (code "30") (name "unconnected-(U1B-IO1-PadJ22)") (class "Default")
      (node (ref "U1") (pin "J22") (pinfunction "IO1_J22") (pintype "bidirectional"))
    )
    (net (code "31") (name "unconnected-(U1B-IO1-PadK16)") (class "Default")
      (node (ref "U1") (pin "K16") (pinfunction "IO1_K16") (pintype "bidirectional"))
    )
    (net (code "32") (name "unconnected-(U1B-IO1-PadK17)") (class "Default")
      (node (ref "U1") (pin "K17") (pinfunction "IO1_K17") (pintype "bidirectional"))
    )
    (net (code "33") (name "unconnected-(U1B-IO1-PadK18)") (class "Default")
      (node (ref "U1") (pin "K18") (pinfunction "IO1_K18") (pintype "bidirectional"))
    )
    (net (code "34") (name "unconnected-(U1B-IO1-PadK19)") (class "Default")
      (node (ref "U1") (pin "K19") (pinfunction "IO1_K19") (pintype "bidirectional"))
    )
    (net (code "35") (name "unconnected-(U1B-IO1-PadK20)") (class "Default")
      (node (ref "U1") (pin "K20") (pinfunction "IO1_K20") (pintype "bidirectional"))
    )
    (net (code "36") (name "unconnected-(U1B-IO1-PadK21)") (class "Default")
      (node (ref "U1") (pin "K21") (pinfunction "IO1_K21") (pintype "bidirectional"))
    )
    (net (code "37") (name "unconnected-(U1B-IO1-PadK22)") (class "Default")
      (node (ref "U1") (pin "K22") (pinfunction "IO1_K22") (pintype "bidirectional"))
    )
    (net (code "38") (name "unconnected-(U1B-IO1-PadL15)") (class "Default")
      (node (ref "U1") (pin "L15") (pinfunction "IO1_L15") (pintype "bidirectional"))
    )
    (net (code "39") (name "unconnected-(U1B-IO1-PadL17)") (class "Default")
      (node (ref "U1") (pin "L17") (pinfunction "IO1_L17") (pintype "bidirectional"))
    )
    (net (code "40") (name "unconnected-(U1B-IO1-PadL19)") (class "Default")
      (node (ref "U1") (pin "L19") (pinfunction "IO1_L19") (pintype "bidirectional"))
    )
    (net (code "41") (name "unconnected-(U1B-IO1-PadL20)") (class "Default")
      (node (ref "U1") (pin "L20") (pinfunction "IO1_L20") (pintype "bidirectional"))
    )
    (net (code "42") (name "unconnected-(U1B-IO1-PadL22)") (class "Default")
      (node (ref "U1") (pin "L22") (pinfunction "IO1_L22") (pintype "bidirectional"))
    )
    (net (code "43") (name "unconnected-(U1B-IO1-PadM16)") (class "Default")
      (node (ref "U1") (pin "M16") (pinfunction "IO1_M16") (pintype "bidirectional"))
    )
    (net (code "44") (name "unconnected-(U1B-IO1-PadM17)") (class "Default")
      (node (ref "U1") (pin "M17") (pinfunction "IO1_M17") (pintype "bidirectional"))
    )
    (net (code "45") (name "unconnected-(U1B-IO1-PadM18)") (class "Default")
      (node (ref "U1") (pin "M18") (pinfunction "IO1_M18") (pintype "bidirectional"))
    )
    (net (code "46") (name "unconnected-(U1B-IO1-PadM19)") (class "Default")
      (node (ref "U1") (pin "M19") (pinfunction "IO1_M19") (pintype "bidirectional"))
    )
    (net (code "47") (name "unconnected-(U1B-IO1-PadM20)") (class "Default")
      (node (ref "U1") (pin "M20") (pinfunction "IO1_M20") (pintype "bidirectional"))
    )
    (net (code "48") (name "unconnected-(U1B-IO1-PadM21)") (class "Default")
      (node (ref "U1") (pin "M21") (pinfunction "IO1_M21") (pintype "bidirectional"))
    )
    (net (code "49") (name "unconnected-(U1B-IO1-PadM22)") (class "Default")
      (node (ref "U1") (pin "M22") (pinfunction "IO1_M22") (pintype "bidirectional"))
    )
    (net (code "50") (name "unconnected-(U1B-IO1-PadN16)") (class "Default")
      (node (ref "U1") (pin "N16") (pinfunction "IO1_N16") (pintype "bidirectional"))
    )
    (net (code "51") (name "unconnected-(U1B-IO1-PadN19)") (class "Default")
      (node (ref "U1") (pin "N19") (pinfunction "IO1_N19") (pintype "bidirectional"))
    )
    (net (code "52") (name "unconnected-(U1B-IO1-PadN20)") (class "Default")
      (node (ref "U1") (pin "N20") (pinfunction "IO1_N20") (pintype "bidirectional"))
    )
    (net (code "53") (name "unconnected-(U1B-IO1-PadP17)") (class "Default")
      (node (ref "U1") (pin "P17") (pinfunction "IO1_P17") (pintype "bidirectional"))
    )
    (net (code "54") (name "unconnected-(U1B-IO1-PadP18)") (class "Default")
      (node (ref "U1") (pin "P18") (pinfunction "IO1_P18") (pintype "bidirectional"))
    )
    (net (code "55") (name "unconnected-(U1B-IO1-PadP19)") (class "Default")
      (node (ref "U1") (pin "P19") (pinfunction "IO1_P19") (pintype "bidirectional"))
    )
    (net (code "56") (name "unconnected-(U1B-IO1-PadP20)") (class "Default")
      (node (ref "U1") (pin "P20") (pinfunction "IO1_P20") (pintype "bidirectional"))
    )
    (net (code "57") (name "unconnected-(U1B-IO1-PadP22)") (class "Default")
      (node (ref "U1") (pin "P22") (pinfunction "IO1_P22") (pintype "bidirectional"))
    )
    (net (code "58") (name "unconnected-(U1B-IO1-PadR19)") (class "Default")
      (node (ref "U1") (pin "R19") (pinfunction "IO1_R19") (pintype "bidirectional"))
    )
    (net (code "59") (name "unconnected-(U1B-IO1-PadR20)") (class "Default")
      (node (ref "U1") (pin "R20") (pinfunction "IO1_R20") (pintype "bidirectional"))
    )
    (net (code "60") (name "unconnected-(U1B-IO1-PadR22)") (class "Default")
      (node (ref "U1") (pin "R22") (pinfunction "IO1_R22") (pintype "bidirectional"))
    )
    (net (code "61") (name "unconnected-(U1B-IO1-PadT19)") (class "Default")
      (node (ref "U1") (pin "T19") (pinfunction "IO1_T19") (pintype "bidirectional"))
    )
    (net (code "62") (name "unconnected-(U1B-IO1-PadT21)") (class "Default")
      (node (ref "U1") (pin "T21") (pinfunction "IO1_T21") (pintype "bidirectional"))
    )
    (net (code "63") (name "unconnected-(U1B-IO1-PadT22)") (class "Default")
      (node (ref "U1") (pin "T22") (pinfunction "IO1_T22") (pintype "bidirectional"))
    )
    (net (code "64") (name "unconnected-(U1B-IO1-PadU19)") (class "Default")
      (node (ref "U1") (pin "U19") (pinfunction "IO1_U19") (pintype "bidirectional"))
    )
    (net (code "65") (name "unconnected-(U1B-IO1-PadU20)") (class "Default")
      (node (ref "U1") (pin "U20") (pinfunction "IO1_U20") (pintype "bidirectional"))
    )
    (net (code "66") (name "unconnected-(U1B-IO1-PadU22)") (class "Default")
      (node (ref "U1") (pin "U22") (pinfunction "IO1_U22") (pintype "bidirectional"))
    )
    (net (code "67") (name "unconnected-(U1B-IO1-PadV20)") (class "Default")
      (node (ref "U1") (pin "V20") (pinfunction "IO1_V20") (pintype "bidirectional"))
    )
    (net (code "68") (name "unconnected-(U1B-IO1-PadV21)") (class "Default")
      (node (ref "U1") (pin "V21") (pinfunction "IO1_V21") (pintype "bidirectional"))
    )
    (net (code "69") (name "unconnected-(U1B-IO1-PadV22)") (class "Default")
      (node (ref "U1") (pin "V22") (pinfunction "IO1_V22") (pintype "bidirectional"))
    )
    (net (code "70") (name "unconnected-(U1B-IO1-PadW20)") (class "Default")
      (node (ref "U1") (pin "W20") (pinfunction "IO1_W20") (pintype "bidirectional"))
    )
    (net (code "71") (name "unconnected-(U1B-IO1-PadW22)") (class "Default")
      (node (ref "U1") (pin "W22") (pinfunction "IO1_W22") (pintype "bidirectional"))
    )
    (net (code "72") (name "unconnected-(U1B-IO3-PadC1)") (class "Default")
      (node (ref "U1") (pin "C1") (pinfunction "IO3_C1") (pintype "bidirectional"))
    )
    (net (code "73") (name "unconnected-(U1B-IO3-PadD1)") (class "Default")
      (node (ref "U1") (pin "D1") (pinfunction "IO3_D1") (pintype "bidirectional"))
    )
    (net (code "74") (name "unconnected-(U1B-IO3-PadE1)") (class "Default")
      (node (ref "U1") (pin "E1") (pinfunction "IO3_E1") (pintype "bidirectional"))
    )
    (net (code "75") (name "unconnected-(U1B-IO3-PadF1)") (class "Default")
      (node (ref "U1") (pin "F1") (pinfunction "IO3_F1") (pintype "bidirectional"))
    )
    (net (code "76") (name "unconnected-(U1B-IO3-PadG1)") (class "Default")
      (node (ref "U1") (pin "G1") (pinfunction "IO3_G1") (pintype "bidirectional"))
    )
    (net (code "77") (name "unconnected-(U1B-IO3-PadG6)") (class "Default")
      (node (ref "U1") (pin "G6") (pinfunction "IO3_G6") (pintype "bidirectional"))
    )
    (net (code "78") (name "unconnected-(U1B-IO3-PadH1)") (class "Default")
      (node (ref "U1") (pin "H1") (pinfunction "IO3_H1") (pintype "bidirectional"))
    )
    (net (code "79") (name "unconnected-(U1B-IO3-PadH2)") (class "Default")
      (node (ref "U1") (pin "H2") (pinfunction "IO3_H2") (pintype "bidirectional"))
    )
    (net (code "80") (name "unconnected-(U1B-IO3-PadH3)") (class "Default")
      (node (ref "U1") (pin "H3") (pinfunction "IO3_H3") (pintype "bidirectional"))
    )
    (net (code "81") (name "unconnected-(U1B-IO3-PadH5)") (class "Default")
      (node (ref "U1") (pin "H5") (pinfunction "IO3_H5") (pintype "bidirectional"))
    )
    (net (code "82") (name "unconnected-(U1B-IO3-PadH6)") (class "Default")
      (node (ref "U1") (pin "H6") (pinfunction "IO3_H6") (pintype "bidirectional"))
    )
    (net (code "83") (name "unconnected-(U1B-IO3-PadH8)") (class "Default")
      (node (ref "U1") (pin "H8") (pinfunction "IO3_H8") (pintype "bidirectional"))
    )
    (net (code "84") (name "unconnected-(U1B-IO3-PadJ1)") (class "Default")
      (node (ref "U1") (pin "J1") (pinfunction "IO3_J1") (pintype "bidirectional"))
    )
    (net (code "85") (name "unconnected-(U1B-IO3-PadJ3)") (class "Default")
      (node (ref "U1") (pin "J3") (pinfunction "IO3_J3") (pintype "bidirectional"))
    )
    (net (code "86") (name "unconnected-(U1B-IO3-PadJ4)") (class "Default")
      (node (ref "U1") (pin "J4") (pinfunction "IO3_J4") (pintype "bidirectional"))
    )
    (net (code "87") (name "unconnected-(U1B-IO3-PadJ6)") (class "Default")
      (node (ref "U1") (pin "J6") (pinfunction "IO3_J6") (pintype "bidirectional"))
    )
    (net (code "88") (name "unconnected-(U1B-IO3-PadJ7)") (class "Default")
      (node (ref "U1") (pin "J7") (pinfunction "IO3_J7") (pintype "bidirectional"))
    )
    (net (code "89") (name "unconnected-(U1B-IO3-PadK1)") (class "Default")
      (node (ref "U1") (pin "K1") (pinfunction "IO3_K1") (pintype "bidirectional"))
    )
    (net (code "90") (name "unconnected-(U1B-IO3-PadK2)") (class "Default")
      (node (ref "U1") (pin "K2") (pinfunction "IO3_K2") (pintype "bidirectional"))
    )
    (net (code "91") (name "unconnected-(U1B-IO3-PadK3)") (class "Default")
      (node (ref "U1") (pin "K3") (pinfunction "IO3_K3") (pintype "bidirectional"))
    )
    (net (code "92") (name "unconnected-(U1B-IO3-PadK4)") (class "Default")
      (node (ref "U1") (pin "K4") (pinfunction "IO3_K4") (pintype "bidirectional"))
    )
    (net (code "93") (name "unconnected-(U1B-IO3-PadK5)") (class "Default")
      (node (ref "U1") (pin "K5") (pinfunction "IO3_K5") (pintype "bidirectional"))
    )
    (net (code "94") (name "unconnected-(U1B-IO3-PadK6)") (class "Default")
      (node (ref "U1") (pin "K6") (pinfunction "IO3_K6") (pintype "bidirectional"))
    )
    (net (code "95") (name "unconnected-(U1B-IO3-PadK7)") (class "Default")
      (node (ref "U1") (pin "K7") (pinfunction "IO3_K7") (pintype "bidirectional"))
    )
    (net (code "96") (name "unconnected-(U1B-IO3-PadK8)") (class "Default")
      (node (ref "U1") (pin "K8") (pinfunction "IO3_K8") (pintype "bidirectional"))
    )
    (net (code "97") (name "unconnected-(U1B-IO3-PadL1)") (class "Default")
      (node (ref "U1") (pin "L1") (pinfunction "IO3_L1") (pintype "bidirectional"))
    )
    (net (code "98") (name "unconnected-(U1B-IO3-PadL3)") (class "Default")
      (node (ref "U1") (pin "L3") (pinfunction "IO3_L3") (pintype "bidirectional"))
    )
    (net (code "99") (name "unconnected-(U1B-IO3-PadL4)") (class "Default")
      (node (ref "U1") (pin "L4") (pinfunction "IO3_L4") (pintype "bidirectional"))
    )
    (net (code "100") (name "unconnected-(U1B-IO3-PadL6)") (class "Default")
      (node (ref "U1") (pin "L6") (pinfunction "IO3_L6") (pintype "bidirectional"))
    )
    (net (code "101") (name "unconnected-(U1B-IO3-PadM1)") (class "Default")
      (node (ref "U1") (pin "M1") (pinfunction "IO3_M1") (pintype "bidirectional"))
    )
    (net (code "102") (name "unconnected-(U1B-IO3-PadM2)") (class "Default")
      (node (ref "U1") (pin "M2") (pinfunction "IO3_M2") (pintype "bidirectional"))
    )
    (net (code "103") (name "unconnected-(U1B-IO3-PadM5)") (class "Default")
      (node (ref "U1") (pin "M5") (pinfunction "IO3_M5") (pintype "bidirectional"))
    )
    (net (code "104") (name "unconnected-(U1B-IO3-PadM6)") (class "Default")
      (node (ref "U1") (pin "M6") (pinfunction "IO3_M6") (pintype "bidirectional"))
    )
    (net (code "105") (name "unconnected-(U1B-IO3-PadM7)") (class "Default")
      (node (ref "U1") (pin "M7") (pinfunction "IO3_M7") (pintype "bidirectional"))
    )
    (net (code "106") (name "unconnected-(U1B-IO3-PadM8)") (class "Default")
      (node (ref "U1") (pin "M8") (pinfunction "IO3_M8") (pintype "bidirectional"))
    )
    (net (code "107") (name "unconnected-(U1B-IO3-PadN1)") (class "Default")
      (node (ref "U1") (pin "N1") (pinfunction "IO3_N1") (pintype "bidirectional"))
    )
    (net (code "108") (name "unconnected-(U1B-IO3-PadN6)") (class "Default")
      (node (ref "U1") (pin "N6") (pinfunction "IO3_N6") (pintype "bidirectional"))
    )
    (net (code "109") (name "unconnected-(U1B-IO3-PadN7)") (class "Default")
      (node (ref "U1") (pin "N7") (pinfunction "IO3_N7") (pintype "bidirectional"))
    )
    (net (code "110") (name "unconnected-(U1B-IO3-PadP1)") (class "Default")
      (node (ref "U1") (pin "P1") (pinfunction "IO3_P1") (pintype "bidirectional"))
    )
    (net (code "111") (name "unconnected-(U1B-IO3-PadP2)") (class "Default")
      (node (ref "U1") (pin "P2") (pinfunction "IO3_P2") (pintype "bidirectional"))
    )
    (net (code "112") (name "unconnected-(U1B-IO3-PadP3)") (class "Default")
      (node (ref "U1") (pin "P3") (pinfunction "IO3_P3") (pintype "bidirectional"))
    )
    (net (code "113") (name "unconnected-(U1B-IO3-PadP4)") (class "Default")
      (node (ref "U1") (pin "P4") (pinfunction "IO3_P4") (pintype "bidirectional"))
    )
    (net (code "114") (name "unconnected-(U1B-IO3-PadP6)") (class "Default")
      (node (ref "U1") (pin "P6") (pinfunction "IO3_P6") (pintype "bidirectional"))
    )
    (net (code "115") (name "unconnected-(U1B-IO3-PadP7)") (class "Default")
      (node (ref "U1") (pin "P7") (pinfunction "IO3_P7") (pintype "bidirectional"))
    )
    (net (code "116") (name "unconnected-(U1B-IO3-PadP8)") (class "Default")
      (node (ref "U1") (pin "P8") (pinfunction "IO3_P8") (pintype "bidirectional"))
    )
    (net (code "117") (name "unconnected-(U1B-IO3-PadR1)") (class "Default")
      (node (ref "U1") (pin "R1") (pinfunction "IO3_R1") (pintype "bidirectional"))
    )
    (net (code "118") (name "unconnected-(U1B-IO3-PadR3)") (class "Default")
      (node (ref "U1") (pin "R3") (pinfunction "IO3_R3") (pintype "bidirectional"))
    )
    (net (code "119") (name "unconnected-(U1B-IO3-PadR4)") (class "Default")
      (node (ref "U1") (pin "R4") (pinfunction "IO3_R4") (pintype "bidirectional"))
    )
    (net (code "120") (name "unconnected-(U1B-IO3-PadT4)") (class "Default")
      (node (ref "U1") (pin "T4") (pinfunction "IO3_T4") (pintype "bidirectional"))
    )
    (net (code "121") (name "unconnected-(U1B-IO3-PadU4)") (class "Default")
      (node (ref "U1") (pin "U4") (pinfunction "IO3_U4") (pintype "bidirectional"))
    )
    (net (code "122") (name "unconnected-(U1F-NC-PadD12)") (class "Default")
      (node (ref "U1") (pin "D12") (pinfunction "NC_D12") (pintype "passive"))
    )
    (net (code "123") (name "unconnected-(U1F-NC-PadD13)") (class "Default")
      (node (ref "U1") (pin "D13") (pinfunction "NC_D13") (pintype "passive"))
    )
    (net (code "124") (name "unconnected-(U1F-NC-PadE8)") (class "Default")
      (node (ref "U1") (pin "E8") (pinfunction "NC_E8") (pintype "passive"))
    )
    (net (code "125") (name "unconnected-(U1F-NC-PadE10)") (class "Default")
      (node (ref "U1") (pin "E10") (pinfunction "NC_E10") (pintype "passive"))
    )
    (net (code "126") (name "unconnected-(U1F-NC-PadE12)") (class "Default")
      (node (ref "U1") (pin "E12") (pinfunction "NC_E12") (pintype "passive"))
    )
    (net (code "127") (name "unconnected-(U1F-NC-PadE14)") (class "Default")
      (node (ref "U1") (pin "E14") (pinfunction "NC_E14") (pintype "passive"))
    )
    (net (code "128") (name "unconnected-(U1F-NC-PadF8)") (class "Default")
      (node (ref "U1") (pin "F8") (pinfunction "NC_F8") (pintype "passive"))
    )
    (net (code "129") (name "unconnected-(U1F-NC-PadF9)") (class "Default")
      (node (ref "U1") (pin "F9") (pinfunction "NC_F9") (pintype "passive"))
    )
    (net (code "130") (name "unconnected-(U1F-NC-PadF10)") (class "Default")
      (node (ref "U1") (pin "F10") (pinfunction "NC_F10") (pintype "passive"))
    )
    (net (code "131") (name "unconnected-(U1F-NC-PadF12)") (class "Default")
      (node (ref "U1") (pin "F12") (pinfunction "NC_F12") (pintype "passive"))
    )
    (net (code "132") (name "unconnected-(U1F-NC-PadF13)") (class "Default")
      (node (ref "U1") (pin "F13") (pinfunction "NC_F13") (pintype "passive"))
    )
    (net (code "133") (name "unconnected-(U1F-NC-PadF14)") (class "Default")
      (node (ref "U1") (pin "F14") (pinfunction "NC_F14") (pintype "passive"))
    )
    (net (code "134") (name "unconnected-(U1F-NC-PadF15)") (class "Default")
      (node (ref "U1") (pin "F15") (pinfunction "NC_F15") (pintype "passive"))
    )
    (net (code "135") (name "unconnected-(U1F-NC-PadG8)") (class "Default")
      (node (ref "U1") (pin "G8") (pinfunction "NC_G8") (pintype "passive"))
    )
    (net (code "136") (name "unconnected-(U1F-NC-PadG9)") (class "Default")
      (node (ref "U1") (pin "G9") (pinfunction "NC_G9") (pintype "passive"))
    )
    (net (code "137") (name "unconnected-(U1F-NC-PadG11)") (class "Default")
      (node (ref "U1") (pin "G11") (pinfunction "NC_G11") (pintype "passive"))
    )
    (net (code "138") (name "unconnected-(U1F-NC-PadG13)") (class "Default")
      (node (ref "U1") (pin "G13") (pinfunction "NC_G13") (pintype "passive"))
    )
    (net (code "139") (name "unconnected-(U1F-NC-PadH10)") (class "Default")
      (node (ref "U1") (pin "H10") (pinfunction "NC_H10") (pintype "passive"))
    )
    (net (code "140") (name "unconnected-(U1F-NC-PadH11)") (class "Default")
      (node (ref "U1") (pin "H11") (pinfunction "NC_H11") (pintype "passive"))
    )
    (net (code "141") (name "unconnected-(U1F-NC-PadH12)") (class "Default")
      (node (ref "U1") (pin "H12") (pinfunction "NC_H12") (pintype "passive"))
    )
    (net (code "142") (name "unconnected-(U1F-NC-PadH13)") (class "Default")
      (node (ref "U1") (pin "H13") (pinfunction "NC_H13") (pintype "passive"))
    )
    (net (code "143") (name "unconnected-(U1F-NC-PadH14)") (class "Default")
      (node (ref "U1") (pin "H14") (pinfunction "NC_H14") (pintype "passive"))
    )
    (net (code "144") (name "unconnected-(U1F-NC-PadP15)") (class "Default")
      (node (ref "U1") (pin "P15") (pinfunction "NC_P15") (pintype "passive"))
    )
    (net (code "145") (name "unconnected-(U1F-NC-PadP16)") (class "Default")
      (node (ref "U1") (pin "P16") (pinfunction "NC_P16") (pintype "passive"))
    )
    (net (code "146") (name "unconnected-(U1F-NC-PadR17)") (class "Default")
      (node (ref "U1") (pin "R17") (pinfunction "NC_R17") (pintype "passive"))
    )
    (net (code "147") (name "unconnected-(U1H-IO2-PadAA16)") (class "Default")
      (node (ref "U1") (pin "AA16") (pinfunction "IO2_AA16") (pintype "bidirectional"))
    )
    (net (code "148") (name "unconnected-(U1H-IO2-PadAA18)") (class "Default")
      (node (ref "U1") (pin "AA18") (pinfunction "IO2_AA18") (pintype "bidirectional"))
    )
    (net (code "149") (name "unconnected-(U1H-IO2-PadAA21)") (class "Default")
      (node (ref "U1") (pin "AA21") (pinfunction "IO2_AA21") (pintype "bidirectional"))
    )
    (net (code "150") (name "unconnected-(U1H-IO2-PadAB15)") (class "Default")
      (node (ref "U1") (pin "AB15") (pinfunction "IO2_AB15") (pintype "bidirectional"))
    )
    (net (code "151") (name "unconnected-(U1H-IO2-PadAB16)") (class "Default")
      (node (ref "U1") (pin "AB16") (pinfunction "IO2_AB16") (pintype "bidirectional"))
    )
    (net (code "152") (name "unconnected-(U1H-IO2-PadAB17)") (class "Default")
      (node (ref "U1") (pin "AB17") (pinfunction "IO2_AB17") (pintype "bidirectional"))
    )
    (net (code "153") (name "unconnected-(U1H-IO2-PadAB18)") (class "Default")
      (node (ref "U1") (pin "AB18") (pinfunction "IO2_AB18") (pintype "bidirectional"))
    )
    (net (code "154") (name "unconnected-(U1H-IO2-PadAB19)") (class "Default")
      (node (ref "U1") (pin "AB19") (pinfunction "IO2_AB19") (pintype "bidirectional"))
    )
    (net (code "155") (name "unconnected-(U1H-IO2-PadR7)") (class "Default")
      (node (ref "U1") (pin "R7") (pinfunction "IO2_R7") (pintype "bidirectional"))
    )
    (net (code "156") (name "unconnected-(U1H-IO2-PadR8)") (class "Default")
      (node (ref "U1") (pin "R8") (pinfunction "IO2_R8") (pintype "bidirectional"))
    )
    (net (code "157") (name "unconnected-(U1H-IO2-PadR9)") (class "Default")
      (node (ref "U1") (pin "R9") (pinfunction "IO2_R9") (pintype "bidirectional"))
    )
    (net (code "158") (name "unconnected-(U1H-IO2-PadR11)") (class "Default")
      (node (ref "U1") (pin "R11") (pinfunction "IO2_R11") (pintype "bidirectional"))
    )
    (net (code "159") (name "unconnected-(U1H-IO2-PadR13)") (class "Default")
      (node (ref "U1") (pin "R13") (pinfunction "IO2_R13") (pintype "bidirectional"))
    )
    (net (code "160") (name "unconnected-(U1H-IO2-PadR15)") (class "Default")
      (node (ref "U1") (pin "R15") (pinfunction "IO2_R15") (pintype "bidirectional"))
    )
    (net (code "161") (name "unconnected-(U1H-IO2-PadR16)") (class "Default")
      (node (ref "U1") (pin "R16") (pinfunction "IO2_R16") (pintype "bidirectional"))
    )
    (net (code "162") (name "unconnected-(U1H-IO2-PadT7)") (class "Default")
      (node (ref "U1") (pin "T7") (pinfunction "IO2_T7") (pintype "bidirectional"))
    )
    (net (code "163") (name "unconnected-(U1H-IO2-PadT8)") (class "Default")
      (node (ref "U1") (pin "T8") (pinfunction "IO2_T8") (pintype "bidirectional"))
    )
    (net (code "164") (name "unconnected-(U1H-IO2-PadT10)") (class "Default")
      (node (ref "U1") (pin "T10") (pinfunction "IO2_T10") (pintype "bidirectional"))
    )
    (net (code "165") (name "unconnected-(U1H-IO2-PadT11)") (class "Default")
      (node (ref "U1") (pin "T11") (pinfunction "IO2_T11") (pintype "bidirectional"))
    )
    (net (code "166") (name "unconnected-(U1H-IO2-PadT12)") (class "Default")
      (node (ref "U1") (pin "T12") (pinfunction "IO2_T12") (pintype "bidirectional"))
    )
    (net (code "167") (name "unconnected-(U1H-IO2-PadT14)") (class "Default")
      (node (ref "U1") (pin "T14") (pinfunction "IO2_T14") (pintype "bidirectional"))
    )
    (net (code "168") (name "unconnected-(U1H-IO2-PadT15)") (class "Default")
      (node (ref "U1") (pin "T15") (pinfunction "IO2_T15") (pintype "bidirectional"))
    )
    (net (code "169") (name "unconnected-(U1H-IO2-PadT16)") (class "Default")
      (node (ref "U1") (pin "T16") (pinfunction "IO2_T16") (pintype "bidirectional"))
    )
    (net (code "170") (name "unconnected-(U1H-IO2-PadT17)") (class "Default")
      (node (ref "U1") (pin "T17") (pinfunction "IO2_T17") (pintype "bidirectional"))
    )
    (net (code "171") (name "unconnected-(U1H-IO2-PadT18)") (class "Default")
      (node (ref "U1") (pin "T18") (pinfunction "IO2_T18") (pintype "bidirectional"))
    )
    (net (code "172") (name "unconnected-(U1H-IO2-PadU6)") (class "Default")
      (node (ref "U1") (pin "U6") (pinfunction "IO2_U6") (pintype "bidirectional"))
    )
    (net (code "173") (name "unconnected-(U1H-IO2-PadU8)") (class "Default")
      (node (ref "U1") (pin "U8") (pinfunction "IO2_U8") (pintype "bidirectional"))
    )
    (net (code "174") (name "unconnected-(U1H-IO2-PadU9)") (class "Default")
      (node (ref "U1") (pin "U9") (pinfunction "IO2_U9") (pintype "bidirectional"))
    )
    (net (code "175") (name "unconnected-(U1H-IO2-PadU12)") (class "Default")
      (node (ref "U1") (pin "U12") (pinfunction "IO2_U12") (pintype "bidirectional"))
    )
    (net (code "176") (name "unconnected-(U1H-IO2-PadU13)") (class "Default")
      (node (ref "U1") (pin "U13") (pinfunction "IO2_U13") (pintype "bidirectional"))
    )
    (net (code "177") (name "unconnected-(U1H-IO2-PadU14)") (class "Default")
      (node (ref "U1") (pin "U14") (pinfunction "IO2_U14") (pintype "bidirectional"))
    )
    (net (code "178") (name "unconnected-(U1H-IO2-PadU16)") (class "Default")
      (node (ref "U1") (pin "U16") (pinfunction "IO2_U16") (pintype "bidirectional"))
    )
    (net (code "179") (name "unconnected-(U1H-IO2-PadU17)") (class "Default")
      (node (ref "U1") (pin "U17") (pinfunction "IO2_U17") (pintype "bidirectional"))
    )
    (net (code "180") (name "unconnected-(U1H-IO2-PadV5)") (class "Default")
      (node (ref "U1") (pin "V5") (pinfunction "IO2_V5") (pintype "bidirectional"))
    )
    (net (code "181") (name "unconnected-(U1H-IO2-PadV11)") (class "Default")
      (node (ref "U1") (pin "V11") (pinfunction "IO2_V11") (pintype "bidirectional"))
    )
    (net (code "182") (name "unconnected-(U1H-IO2-PadV15)") (class "Default")
      (node (ref "U1") (pin "V15") (pinfunction "IO2_V15") (pintype "bidirectional"))
    )
    (net (code "183") (name "unconnected-(U1H-IO2-PadV17)") (class "Default")
      (node (ref "U1") (pin "V17") (pinfunction "IO2_V17") (pintype "bidirectional"))
    )
    (net (code "184") (name "unconnected-(U1H-IO2-PadW9)") (class "Default")
      (node (ref "U1") (pin "W9") (pinfunction "IO2_W9") (pintype "bidirectional"))
    )
    (net (code "185") (name "unconnected-(U1H-IO2-PadW10)") (class "Default")
      (node (ref "U1") (pin "W10") (pinfunction "IO2_W10") (pintype "bidirectional"))
    )
    (net (code "186") (name "unconnected-(U1H-IO2-PadW11)") (class "Default")
      (node (ref "U1") (pin "W11") (pinfunction "IO2_W11") (pintype "bidirectional"))
    )
    (net (code "187") (name "unconnected-(U1H-IO2-PadW14)") (class "Default")
      (node (ref "U1") (pin "W14") (pinfunction "IO2_W14") (pintype "bidirectional"))
    )
    (net (code "188") (name "unconnected-(U1H-IO2-PadW15)") (class "Default")
      (node (ref "U1") (pin "W15") (pinfunction "IO2_W15") (pintype "bidirectional"))
    )
    (net (code "189") (name "unconnected-(U1H-IO2-PadY18)") (class "Default")
      (node (ref "U1") (pin "Y18") (pinfunction "IO2_Y18") (pintype "bidirectional"))
    )
    (net (code "190") (name "unconnected-(U3B-NC-Pad16)") (class "Default")
      (node (ref "U3") (pin "16") (pinfunction "NC_16") (pintype "passive"))
    )
  )
)
